# GB-Cartridge-Reader-Writer.net
KiCad netlist of a schematic drawn in EAGLE
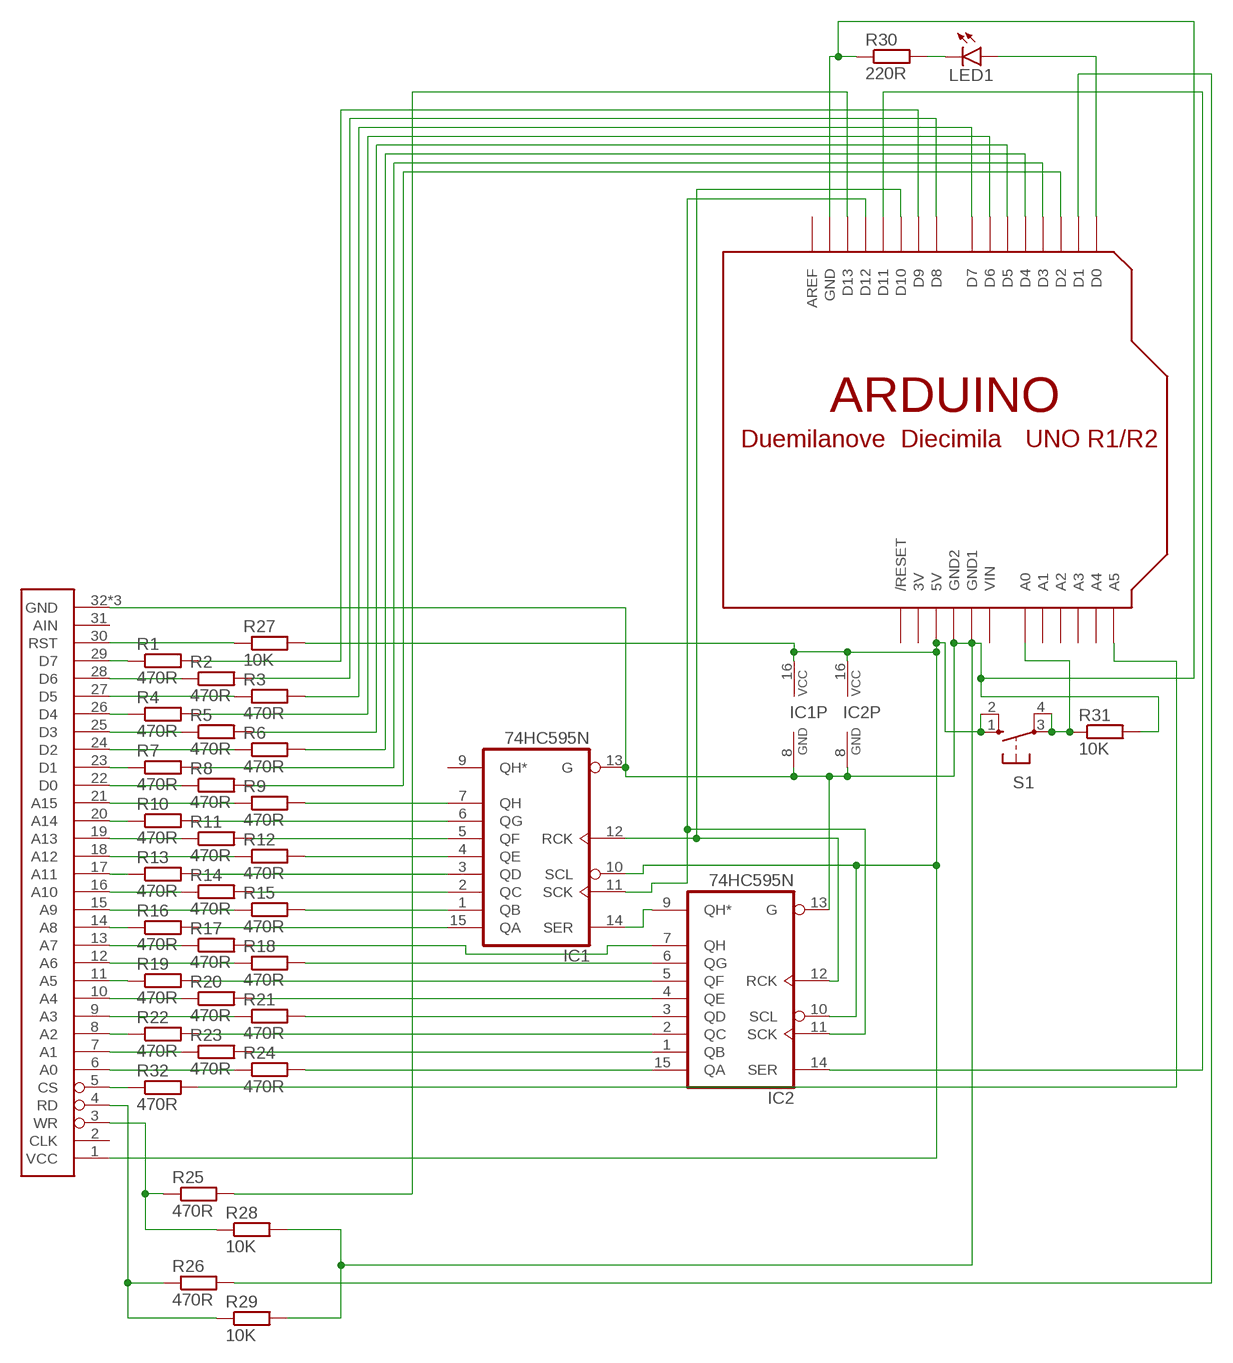
[diagram p0: schematic, sheet 1]

(export (version "E")
  (design (tool "Eeschema 10.0.6"))
  (components
    (comp (ref "IC1")
      (value "74HC595N")
      (footprint "eagle-import:DIL16")
      (libsource (lib "eagle-import") (part "74595NHC"))
    )
    (comp (ref "IC2")
      (value "74HC595N")
      (footprint "eagle-import:DIL16")
      (libsource (lib "eagle-import") (part "74595NHC"))
    )
    (comp (ref "LED1")
      (value "LED5MM")
      (footprint "eagle-import:LED5MM")
      (libsource (lib "eagle-import") (part "LED5MM"))
    )
    (comp (ref "R1")
      (value "470R")
      (footprint "eagle-import:0207_10")
      (libsource (lib "eagle-import") (part "R-EU_0207/10"))
    )
    (comp (ref "R2")
      (value "470R")
      (footprint "eagle-import:0207_10")
      (libsource (lib "eagle-import") (part "R-EU_0207/10"))
    )
    (comp (ref "R3")
      (value "470R")
      (footprint "eagle-import:0207_10")
      (libsource (lib "eagle-import") (part "R-EU_0207/10"))
    )
    (comp (ref "R4")
      (value "470R")
      (footprint "eagle-import:0207_10")
      (libsource (lib "eagle-import") (part "R-EU_0207/10"))
    )
    (comp (ref "R5")
      (value "470R")
      (footprint "eagle-import:0207_10")
      (libsource (lib "eagle-import") (part "R-EU_0207/10"))
    )
    (comp (ref "R6")
      (value "470R")
      (footprint "eagle-import:0207_10")
      (libsource (lib "eagle-import") (part "R-EU_0207/10"))
    )
    (comp (ref "R7")
      (value "470R")
      (footprint "eagle-import:0207_10")
      (libsource (lib "eagle-import") (part "R-EU_0207/10"))
    )
    (comp (ref "R8")
      (value "470R")
      (footprint "eagle-import:0207_10")
      (libsource (lib "eagle-import") (part "R-EU_0207/10"))
    )
    (comp (ref "R9")
      (value "470R")
      (footprint "eagle-import:0207_10")
      (libsource (lib "eagle-import") (part "R-EU_0207/10"))
    )
    (comp (ref "R10")
      (value "470R")
      (footprint "eagle-import:0207_10")
      (libsource (lib "eagle-import") (part "R-EU_0207/10"))
    )
    (comp (ref "R11")
      (value "470R")
      (footprint "eagle-import:0207_10")
      (libsource (lib "eagle-import") (part "R-EU_0207/10"))
    )
    (comp (ref "R12")
      (value "470R")
      (footprint "eagle-import:0207_10")
      (libsource (lib "eagle-import") (part "R-EU_0207/10"))
    )
    (comp (ref "R13")
      (value "470R")
      (footprint "eagle-import:0207_10")
      (libsource (lib "eagle-import") (part "R-EU_0207/10"))
    )
    (comp (ref "R14")
      (value "470R")
      (footprint "eagle-import:0207_10")
      (libsource (lib "eagle-import") (part "R-EU_0207/10"))
    )
    (comp (ref "R15")
      (value "470R")
      (footprint "eagle-import:0207_10")
      (libsource (lib "eagle-import") (part "R-EU_0207/10"))
    )
    (comp (ref "R16")
      (value "470R")
      (footprint "eagle-import:0207_10")
      (libsource (lib "eagle-import") (part "R-EU_0207/10"))
    )
    (comp (ref "R17")
      (value "470R")
      (footprint "eagle-import:0207_10")
      (libsource (lib "eagle-import") (part "R-EU_0207/10"))
    )
    (comp (ref "R18")
      (value "470R")
      (footprint "eagle-import:0207_10")
      (libsource (lib "eagle-import") (part "R-EU_0207/10"))
    )
    (comp (ref "R19")
      (value "470R")
      (footprint "eagle-import:0207_10")
      (libsource (lib "eagle-import") (part "R-EU_0207/10"))
    )
    (comp (ref "R20")
      (value "470R")
      (footprint "eagle-import:0207_10")
      (libsource (lib "eagle-import") (part "R-EU_0207/10"))
    )
    (comp (ref "R21")
      (value "470R")
      (footprint "eagle-import:0207_10")
      (libsource (lib "eagle-import") (part "R-EU_0207/10"))
    )
    (comp (ref "R22")
      (value "470R")
      (footprint "eagle-import:0207_10")
      (libsource (lib "eagle-import") (part "R-EU_0207/10"))
    )
    (comp (ref "R23")
      (value "470R")
      (footprint "eagle-import:0207_10")
      (libsource (lib "eagle-import") (part "R-EU_0207/10"))
    )
    (comp (ref "R24")
      (value "470R")
      (footprint "eagle-import:0207_10")
      (libsource (lib "eagle-import") (part "R-EU_0207/10"))
    )
    (comp (ref "R25")
      (value "470R")
      (footprint "eagle-import:0207_10")
      (libsource (lib "eagle-import") (part "R-EU_0207/10"))
    )
    (comp (ref "R26")
      (value "470R")
      (footprint "eagle-import:0207_10")
      (libsource (lib "eagle-import") (part "R-EU_0207/10"))
    )
    (comp (ref "R27")
      (value "10K")
      (footprint "eagle-import:0207_10")
      (libsource (lib "eagle-import") (part "R-EU_0207/10"))
    )
    (comp (ref "R28")
      (value "10K")
      (footprint "eagle-import:0207_10")
      (libsource (lib "eagle-import") (part "R-EU_0207/10"))
    )
    (comp (ref "R29")
      (value "10K")
      (footprint "eagle-import:0207_10")
      (libsource (lib "eagle-import") (part "R-EU_0207/10"))
    )
    (comp (ref "R30")
      (value "220R")
      (footprint "eagle-import:0207_10")
      (libsource (lib "eagle-import") (part "R-EU_0207/10"))
    )
    (comp (ref "R31")
      (value "10K")
      (footprint "eagle-import:0207_10")
      (libsource (lib "eagle-import") (part "R-EU_0207/10"))
    )
    (comp (ref "R32")
      (value "470R")
      (footprint "eagle-import:0207_10")
      (libsource (lib "eagle-import") (part "R-EU_0207/10"))
    )
    (comp (ref "S1")
      (value "10-XX")
      (footprint "eagle-import:B3F-10XX")
      (fields (field (name "MPN") "B3F-1000"))
      (libsource (lib "eagle-import") (part "10-XX"))
    )
    (comp (ref "U$1")
      (value "ARDUINO-NOHOLE")
      (footprint "eagle-import:ARDUINO-NOHOLE")
      (libsource (lib "eagle-import") (part "ARDUINO-NOHOLE"))
    )
    (comp (ref "U$2")
      (value "GB-CARTRIDGE-SLOTV3")
      (footprint "eagle-import:GB-CARTRIDGE-SLOT-3")
      (libsource (lib "eagle-import") (part "GB-CARTRIDGE-SLOTV3"))
    )
  )
  (nets
    (net (code "1") (name "/3V") (class "Default")
      (node (ref "U$1") (pin "3V") (pinfunction "3V_3V") (pintype "power_in"))
    )
    (net (code "2") (name "/VIN") (class "Default")
      (node (ref "U$1") (pin "VIN") (pinfunction "VIN_VIN") (pintype "power_in"))
    )
    (net (code "3") (name "Net-(IC1A-G)") (class "Default")
      (node (ref "IC1") (pin "13") (pinfunction "G_13") (pintype "input"))
      (node (ref "IC1") (pin "8") (pinfunction "GND_8") (pintype "power_in"))
      (node (ref "IC2") (pin "13") (pinfunction "G_13") (pintype "input"))
      (node (ref "IC2") (pin "8") (pinfunction "GND_8") (pintype "power_in"))
      (node (ref "R28") (pin "2") (pinfunction "2_2") (pintype "passive"))
      (node (ref "R29") (pin "2") (pinfunction "2_2") (pintype "passive"))
      (node (ref "R30") (pin "1") (pinfunction "1_1") (pintype "passive"))
      (node (ref "R31") (pin "2") (pinfunction "2_2") (pintype "passive"))
      (node (ref "U$1") (pin "GND") (pinfunction "GND_GND") (pintype "power_in"))
      (node (ref "U$1") (pin "GND1") (pinfunction "GND1_GND1") (pintype "power_in"))
      (node (ref "U$1") (pin "GND2") (pinfunction "GND2_GND2") (pintype "power_in"))
      (node (ref "U$2") (pin "32") (pinfunction "GND_32") (pintype "bidirectional"))
      (node (ref "U$2") (pin "PAD1") (pinfunction "GND_PAD1") (pintype "bidirectional"))
      (node (ref "U$2") (pin "PAD2") (pinfunction "GND_PAD2") (pintype "bidirectional"))
    )
    (net (code "4") (name "Net-(IC1A-QA)") (class "Default")
      (node (ref "IC1") (pin "15") (pinfunction "QA_15") (pintype "tri_state"))
      (node (ref "R16") (pin "2") (pinfunction "2_2") (pintype "passive"))
    )
    (net (code "5") (name "Net-(IC1A-QB)") (class "Default")
      (node (ref "IC1") (pin "1") (pinfunction "QB_1") (pintype "tri_state"))
      (node (ref "R15") (pin "2") (pinfunction "2_2") (pintype "passive"))
    )
    (net (code "6") (name "Net-(IC1A-QC)") (class "Default")
      (node (ref "IC1") (pin "2") (pinfunction "QC_2") (pintype "tri_state"))
      (node (ref "R14") (pin "2") (pinfunction "2_2") (pintype "passive"))
    )
    (net (code "7") (name "Net-(IC1A-QD)") (class "Default")
      (node (ref "IC1") (pin "3") (pinfunction "QD_3") (pintype "tri_state"))
      (node (ref "R13") (pin "2") (pinfunction "2_2") (pintype "passive"))
    )
    (net (code "8") (name "Net-(IC1A-QE)") (class "Default")
      (node (ref "IC1") (pin "4") (pinfunction "QE_4") (pintype "tri_state"))
      (node (ref "R12") (pin "2") (pinfunction "2_2") (pintype "passive"))
    )
    (net (code "9") (name "Net-(IC1A-QF)") (class "Default")
      (node (ref "IC1") (pin "5") (pinfunction "QF_5") (pintype "tri_state"))
      (node (ref "R11") (pin "2") (pinfunction "2_2") (pintype "passive"))
    )
    (net (code "10") (name "Net-(IC1A-QG)") (class "Default")
      (node (ref "IC1") (pin "6") (pinfunction "QG_6") (pintype "tri_state"))
      (node (ref "R10") (pin "2") (pinfunction "2_2") (pintype "passive"))
    )
    (net (code "11") (name "Net-(IC1A-QH)") (class "Default")
      (node (ref "IC1") (pin "7") (pinfunction "QH_7") (pintype "tri_state"))
      (node (ref "R9") (pin "2") (pinfunction "2_2") (pintype "passive"))
    )
    (net (code "12") (name "Net-(IC1A-RCK)") (class "Default")
      (node (ref "IC1") (pin "12") (pinfunction "RCK_12") (pintype "input"))
      (node (ref "IC2") (pin "12") (pinfunction "RCK_12") (pintype "input"))
      (node (ref "U$1") (pin "D10") (pinfunction "D10_D10") (pintype "bidirectional"))
    )
    (net (code "13") (name "Net-(IC1A-SCK)") (class "Default")
      (node (ref "IC1") (pin "11") (pinfunction "SCK_11") (pintype "input"))
      (node (ref "IC2") (pin "11") (pinfunction "SCK_11") (pintype "input"))
      (node (ref "U$1") (pin "D12") (pinfunction "D12_D12") (pintype "bidirectional"))
    )
    (net (code "14") (name "Net-(IC1A-SCL)") (class "Default")
      (node (ref "IC1") (pin "10") (pinfunction "SCL_10") (pintype "input"))
      (node (ref "IC1") (pin "16") (pinfunction "VCC_16") (pintype "power_in"))
      (node (ref "IC2") (pin "10") (pinfunction "SCL_10") (pintype "input"))
      (node (ref "IC2") (pin "16") (pinfunction "VCC_16") (pintype "power_in"))
      (node (ref "R27") (pin "2") (pinfunction "2_2") (pintype "passive"))
      (node (ref "S1") (pin "1") (pinfunction "S_1") (pintype "passive"))
      (node (ref "S1") (pin "2") (pinfunction "S1_2") (pintype "passive"))
      (node (ref "U$1") (pin "5V") (pinfunction "5V_5V") (pintype "power_in"))
      (node (ref "U$2") (pin "1") (pinfunction "VCC_1") (pintype "bidirectional"))
    )
    (net (code "15") (name "Net-(IC1A-SER)") (class "Default")
      (node (ref "IC1") (pin "14") (pinfunction "SER_14") (pintype "input"))
      (node (ref "IC2") (pin "9") (pinfunction "QH*_9") (pintype "tri_state"))
    )
    (net (code "16") (name "Net-(IC2A-QA)") (class "Default")
      (node (ref "IC2") (pin "15") (pinfunction "QA_15") (pintype "tri_state"))
      (node (ref "R24") (pin "2") (pinfunction "2_2") (pintype "passive"))
    )
    (net (code "17") (name "Net-(IC2A-QB)") (class "Default")
      (node (ref "IC2") (pin "1") (pinfunction "QB_1") (pintype "tri_state"))
      (node (ref "R23") (pin "2") (pinfunction "2_2") (pintype "passive"))
    )
    (net (code "18") (name "Net-(IC2A-QC)") (class "Default")
      (node (ref "IC2") (pin "2") (pinfunction "QC_2") (pintype "tri_state"))
      (node (ref "R22") (pin "2") (pinfunction "2_2") (pintype "passive"))
    )
    (net (code "19") (name "Net-(IC2A-QD)") (class "Default")
      (node (ref "IC2") (pin "3") (pinfunction "QD_3") (pintype "tri_state"))
      (node (ref "R21") (pin "2") (pinfunction "2_2") (pintype "passive"))
    )
    (net (code "20") (name "Net-(IC2A-QE)") (class "Default")
      (node (ref "IC2") (pin "4") (pinfunction "QE_4") (pintype "tri_state"))
      (node (ref "R20") (pin "2") (pinfunction "2_2") (pintype "passive"))
    )
    (net (code "21") (name "Net-(IC2A-QF)") (class "Default")
      (node (ref "IC2") (pin "5") (pinfunction "QF_5") (pintype "tri_state"))
      (node (ref "R19") (pin "2") (pinfunction "2_2") (pintype "passive"))
    )
    (net (code "22") (name "Net-(IC2A-QG)") (class "Default")
      (node (ref "IC2") (pin "6") (pinfunction "QG_6") (pintype "tri_state"))
      (node (ref "R18") (pin "2") (pinfunction "2_2") (pintype "passive"))
    )
    (net (code "23") (name "Net-(IC2A-QH)") (class "Default")
      (node (ref "IC2") (pin "7") (pinfunction "QH_7") (pintype "tri_state"))
      (node (ref "R17") (pin "2") (pinfunction "2_2") (pintype "passive"))
    )
    (net (code "24") (name "Net-(IC2A-SER)") (class "Default")
      (node (ref "IC2") (pin "14") (pinfunction "SER_14") (pintype "input"))
      (node (ref "U$1") (pin "D11") (pinfunction "D11_D11") (pintype "bidirectional"))
    )
    (net (code "25") (name "Net-(LED1-C)") (class "Default")
      (node (ref "LED1") (pin "K") (pinfunction "C_K") (pintype "passive"))
      (node (ref "R30") (pin "2") (pinfunction "2_2") (pintype "passive"))
    )
    (net (code "26") (name "Net-(LED1-PadA)") (class "Default")
      (node (ref "LED1") (pin "A") (pinfunction "A_A") (pintype "passive"))
      (node (ref "U$1") (pin "D0") (pinfunction "D0_D0") (pintype "bidirectional"))
    )
    (net (code "27") (name "Net-(R1-Pad2)") (class "Default")
      (node (ref "R1") (pin "2") (pinfunction "2_2") (pintype "passive"))
      (node (ref "U$1") (pin "D9") (pinfunction "D9_D9") (pintype "bidirectional"))
    )
    (net (code "28") (name "Net-(R2-Pad2)") (class "Default")
      (node (ref "R2") (pin "2") (pinfunction "2_2") (pintype "passive"))
      (node (ref "U$1") (pin "D8") (pinfunction "D8_D8") (pintype "bidirectional"))
    )
    (net (code "29") (name "Net-(R3-Pad2)") (class "Default")
      (node (ref "R3") (pin "2") (pinfunction "2_2") (pintype "passive"))
      (node (ref "U$1") (pin "D7") (pinfunction "D7_D7") (pintype "bidirectional"))
    )
    (net (code "30") (name "Net-(R4-Pad2)") (class "Default")
      (node (ref "R4") (pin "2") (pinfunction "2_2") (pintype "passive"))
      (node (ref "U$1") (pin "D6") (pinfunction "D6_D6") (pintype "bidirectional"))
    )
    (net (code "31") (name "Net-(R5-Pad2)") (class "Default")
      (node (ref "R5") (pin "2") (pinfunction "2_2") (pintype "passive"))
      (node (ref "U$1") (pin "D5") (pinfunction "D5_D5") (pintype "bidirectional"))
    )
    (net (code "32") (name "Net-(R6-Pad2)") (class "Default")
      (node (ref "R6") (pin "2") (pinfunction "2_2") (pintype "passive"))
      (node (ref "U$1") (pin "D4") (pinfunction "D4_D4") (pintype "bidirectional"))
    )
    (net (code "33") (name "Net-(R7-Pad2)") (class "Default")
      (node (ref "R7") (pin "2") (pinfunction "2_2") (pintype "passive"))
      (node (ref "U$1") (pin "D3") (pinfunction "D3_D3") (pintype "bidirectional"))
    )
    (net (code "34") (name "Net-(R8-Pad2)") (class "Default")
      (node (ref "R8") (pin "2") (pinfunction "2_2") (pintype "passive"))
      (node (ref "U$1") (pin "D2") (pinfunction "D2_D2") (pintype "bidirectional"))
    )
    (net (code "35") (name "Net-(R25-Pad2)") (class "Default")
      (node (ref "R25") (pin "2") (pinfunction "2_2") (pintype "passive"))
      (node (ref "U$1") (pin "D13") (pinfunction "D13_D13") (pintype "bidirectional"))
    )
    (net (code "36") (name "Net-(R26-Pad2)") (class "Default")
      (node (ref "R26") (pin "2") (pinfunction "2_2") (pintype "passive"))
      (node (ref "U$1") (pin "D1") (pinfunction "D1_D1") (pintype "bidirectional"))
    )
    (net (code "37") (name "Net-(R32-Pad2)") (class "Default")
      (node (ref "R32") (pin "2") (pinfunction "2_2") (pintype "passive"))
      (node (ref "U$1") (pin "A5") (pinfunction "A5_A5") (pintype "bidirectional"))
    )
    (net (code "38") (name "Net-(S1-P)") (class "Default")
      (node (ref "R31") (pin "1") (pinfunction "1_1") (pintype "passive"))
      (node (ref "S1") (pin "3") (pinfunction "P_3") (pintype "passive"))
      (node (ref "S1") (pin "4") (pinfunction "P1_4") (pintype "passive"))
      (node (ref "U$1") (pin "A0") (pinfunction "A0_A0") (pintype "bidirectional"))
    )
    (net (code "39") (name "Net-(U$2-A0)") (class "Default")
      (node (ref "R24") (pin "1") (pinfunction "1_1") (pintype "passive"))
      (node (ref "U$2") (pin "6") (pinfunction "A0_6") (pintype "bidirectional"))
    )
    (net (code "40") (name "Net-(U$2-A1)") (class "Default")
      (node (ref "R23") (pin "1") (pinfunction "1_1") (pintype "passive"))
      (node (ref "U$2") (pin "7") (pinfunction "A1_7") (pintype "bidirectional"))
    )
    (net (code "41") (name "Net-(U$2-A2)") (class "Default")
      (node (ref "R22") (pin "1") (pinfunction "1_1") (pintype "passive"))
      (node (ref "U$2") (pin "8") (pinfunction "A2_8") (pintype "bidirectional"))
    )
    (net (code "42") (name "Net-(U$2-A3)") (class "Default")
      (node (ref "R21") (pin "1") (pinfunction "1_1") (pintype "passive"))
      (node (ref "U$2") (pin "9") (pinfunction "A3_9") (pintype "bidirectional"))
    )
    (net (code "43") (name "Net-(U$2-A4)") (class "Default")
      (node (ref "R20") (pin "1") (pinfunction "1_1") (pintype "passive"))
      (node (ref "U$2") (pin "10") (pinfunction "A4_10") (pintype "bidirectional"))
    )
    (net (code "44") (name "Net-(U$2-A5)") (class "Default")
      (node (ref "R19") (pin "1") (pinfunction "1_1") (pintype "passive"))
      (node (ref "U$2") (pin "11") (pinfunction "A5_11") (pintype "bidirectional"))
    )
    (net (code "45") (name "Net-(U$2-A6)") (class "Default")
      (node (ref "R18") (pin "1") (pinfunction "1_1") (pintype "passive"))
      (node (ref "U$2") (pin "12") (pinfunction "A6_12") (pintype "bidirectional"))
    )
    (net (code "46") (name "Net-(U$2-A7)") (class "Default")
      (node (ref "R17") (pin "1") (pinfunction "1_1") (pintype "passive"))
      (node (ref "U$2") (pin "13") (pinfunction "A7_13") (pintype "bidirectional"))
    )
    (net (code "47") (name "Net-(U$2-A8)") (class "Default")
      (node (ref "R16") (pin "1") (pinfunction "1_1") (pintype "passive"))
      (node (ref "U$2") (pin "14") (pinfunction "A8_14") (pintype "bidirectional"))
    )
    (net (code "48") (name "Net-(U$2-A9)") (class "Default")
      (node (ref "R15") (pin "1") (pinfunction "1_1") (pintype "passive"))
      (node (ref "U$2") (pin "15") (pinfunction "A9_15") (pintype "bidirectional"))
    )
    (net (code "49") (name "Net-(U$2-A10)") (class "Default")
      (node (ref "R14") (pin "1") (pinfunction "1_1") (pintype "passive"))
      (node (ref "U$2") (pin "16") (pinfunction "A10_16") (pintype "bidirectional"))
    )
    (net (code "50") (name "Net-(U$2-A11)") (class "Default")
      (node (ref "R13") (pin "1") (pinfunction "1_1") (pintype "passive"))
      (node (ref "U$2") (pin "17") (pinfunction "A11_17") (pintype "bidirectional"))
    )
    (net (code "51") (name "Net-(U$2-A12)") (class "Default")
      (node (ref "R12") (pin "1") (pinfunction "1_1") (pintype "passive"))
      (node (ref "U$2") (pin "18") (pinfunction "A12_18") (pintype "bidirectional"))
    )
    (net (code "52") (name "Net-(U$2-A13)") (class "Default")
      (node (ref "R11") (pin "1") (pinfunction "1_1") (pintype "passive"))
      (node (ref "U$2") (pin "19") (pinfunction "A13_19") (pintype "bidirectional"))
    )
    (net (code "53") (name "Net-(U$2-A14)") (class "Default")
      (node (ref "R10") (pin "1") (pinfunction "1_1") (pintype "passive"))
      (node (ref "U$2") (pin "20") (pinfunction "A14_20") (pintype "bidirectional"))
    )
    (net (code "54") (name "Net-(U$2-A15)") (class "Default")
      (node (ref "R9") (pin "1") (pinfunction "1_1") (pintype "passive"))
      (node (ref "U$2") (pin "21") (pinfunction "A15_21") (pintype "bidirectional"))
    )
    (net (code "55") (name "Net-(U$2-CS)") (class "Default")
      (node (ref "R32") (pin "1") (pinfunction "1_1") (pintype "passive"))
      (node (ref "U$2") (pin "5") (pinfunction "CS_5") (pintype "bidirectional"))
    )
    (net (code "56") (name "Net-(U$2-D0)") (class "Default")
      (node (ref "R8") (pin "1") (pinfunction "1_1") (pintype "passive"))
      (node (ref "U$2") (pin "22") (pinfunction "D0_22") (pintype "bidirectional"))
    )
    (net (code "57") (name "Net-(U$2-D1)") (class "Default")
      (node (ref "R7") (pin "1") (pinfunction "1_1") (pintype "passive"))
      (node (ref "U$2") (pin "23") (pinfunction "D1_23") (pintype "bidirectional"))
    )
    (net (code "58") (name "Net-(U$2-D2)") (class "Default")
      (node (ref "R6") (pin "1") (pinfunction "1_1") (pintype "passive"))
      (node (ref "U$2") (pin "24") (pinfunction "D2_24") (pintype "bidirectional"))
    )
    (net (code "59") (name "Net-(U$2-D3)") (class "Default")
      (node (ref "R5") (pin "1") (pinfunction "1_1") (pintype "passive"))
      (node (ref "U$2") (pin "25") (pinfunction "D3_25") (pintype "bidirectional"))
    )
    (net (code "60") (name "Net-(U$2-D4)") (class "Default")
      (node (ref "R4") (pin "1") (pinfunction "1_1") (pintype "passive"))
      (node (ref "U$2") (pin "26") (pinfunction "D4_26") (pintype "bidirectional"))
    )
    (net (code "61") (name "Net-(U$2-D5)") (class "Default")
      (node (ref "R3") (pin "1") (pinfunction "1_1") (pintype "passive"))
      (node (ref "U$2") (pin "27") (pinfunction "D5_27") (pintype "bidirectional"))
    )
    (net (code "62") (name "Net-(U$2-D6)") (class "Default")
      (node (ref "R2") (pin "1") (pinfunction "1_1") (pintype "passive"))
      (node (ref "U$2") (pin "28") (pinfunction "D6_28") (pintype "bidirectional"))
    )
    (net (code "63") (name "Net-(U$2-D7)") (class "Default")
      (node (ref "R1") (pin "1") (pinfunction "1_1") (pintype "passive"))
      (node (ref "U$2") (pin "29") (pinfunction "D7_29") (pintype "bidirectional"))
    )
    (net (code "64") (name "Net-(U$2-RD)") (class "Default")
      (node (ref "R26") (pin "1") (pinfunction "1_1") (pintype "passive"))
      (node (ref "R29") (pin "1") (pinfunction "1_1") (pintype "passive"))
      (node (ref "U$2") (pin "4") (pinfunction "RD_4") (pintype "bidirectional"))
    )
    (net (code "65") (name "Net-(U$2-RST)") (class "Default")
      (node (ref "R27") (pin "1") (pinfunction "1_1") (pintype "passive"))
      (node (ref "U$2") (pin "30") (pinfunction "RST_30") (pintype "bidirectional"))
    )
    (net (code "66") (name "Net-(U$2-WR)") (class "Default")
      (node (ref "R25") (pin "1") (pinfunction "1_1") (pintype "passive"))
      (node (ref "R28") (pin "1") (pinfunction "1_1") (pintype "passive"))
      (node (ref "U$2") (pin "3") (pinfunction "WR_3") (pintype "bidirectional"))
    )
    (net (code "67") (name "unconnected-(IC1A-QH*-Pad9)") (class "Default")
      (node (ref "IC1") (pin "9") (pinfunction "QH*_9") (pintype "tri_state"))
    )
    (net (code "68") (name "unconnected-(U$1-PadA1)") (class "Default")
      (node (ref "U$1") (pin "A1") (pinfunction "A1_A1") (pintype "bidirectional"))
    )
    (net (code "69") (name "unconnected-(U$1-PadA2)") (class "Default")
      (node (ref "U$1") (pin "A2") (pinfunction "A2_A2") (pintype "bidirectional"))
    )
    (net (code "70") (name "unconnected-(U$1-PadA3)") (class "Default")
      (node (ref "U$1") (pin "A3") (pinfunction "A3_A3") (pintype "bidirectional"))
    )
    (net (code "71") (name "unconnected-(U$1-PadA4)") (class "Default")
      (node (ref "U$1") (pin "A4") (pinfunction "A4_A4") (pintype "bidirectional"))
    )
    (net (code "72") (name "unconnected-(U$1-PadAREF)") (class "Default")
      (node (ref "U$1") (pin "AREF") (pinfunction "AREF_AREF") (pintype "bidirectional"))
    )
    (net (code "73") (name "unconnected-(U$1-{slash}RESET-PadRESET)") (class "Default")
      (node (ref "U$1") (pin "RESET") (pinfunction "/RESET_RESET") (pintype "bidirectional"))
    )
    (net (code "74") (name "unconnected-(U$2-AIN-Pad31)") (class "Default")
      (node (ref "U$2") (pin "31") (pinfunction "AIN_31") (pintype "bidirectional"))
    )
    (net (code "75") (name "unconnected-(U$2-CLK-Pad2)") (class "Default")
      (node (ref "U$2") (pin "2") (pinfunction "CLK_2") (pintype "bidirectional"))
    )
  )
)
